# xbee-smd-breakout-1.net
KiCad netlist of a schematic drawn in EAGLE
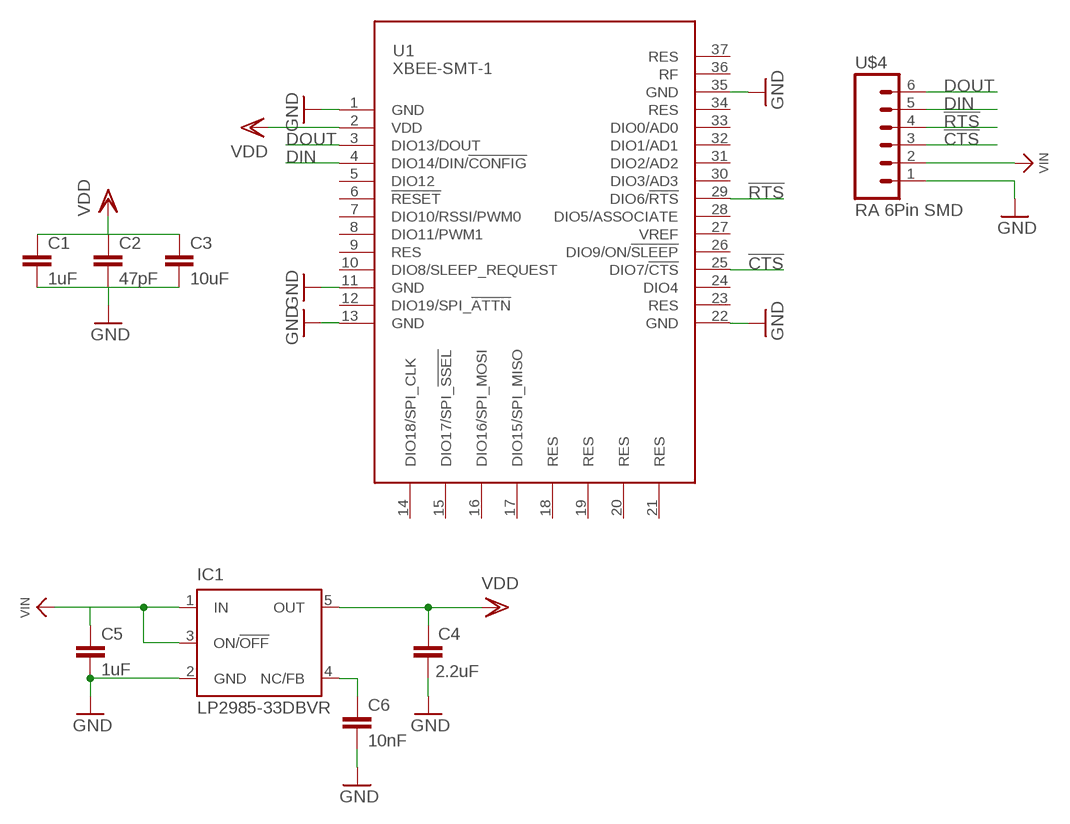
[diagram p0: schematic, sheet 1]

(export (version "E")
  (design (tool "Eeschema 10.0.6"))
  (components
    (comp (ref "C1")
      (value "1uF")
      (footprint "eagle-import:C0805")
      (libsource (lib "eagle-import") (part "C"))
    )
    (comp (ref "C2")
      (value "47pF")
      (footprint "eagle-import:C0805")
      (libsource (lib "eagle-import") (part "C"))
    )
    (comp (ref "C3")
      (value "10uF")
      (footprint "eagle-import:C0805")
      (libsource (lib "eagle-import") (part "C"))
    )
    (comp (ref "C4")
      (value "2.2uF")
      (footprint "eagle-import:C0805")
      (fields (field (name "MF") "MULTICOMP") (field (name "MPN") "MC0805B104K500CT"))
      (libsource (lib "eagle-import") (part "C-EUC0805"))
    )
    (comp (ref "C5")
      (value "1uF")
      (footprint "eagle-import:C0805")
      (libsource (lib "eagle-import") (part "C"))
    )
    (comp (ref "C6")
      (value "10nF")
      (footprint "eagle-import:C0805")
      (libsource (lib "eagle-import") (part "C"))
    )
    (comp (ref "IC1")
      (value "LP2985-33DBVR")
      (footprint "eagle-import:SOT23-DBV")
      (fields (field (name "MF") "ANALOG DEVICES") (field (name "MPN") "ADP3309ARTZ-3.3-R7"))
      (libsource (lib "eagle-import") (part "LP2985-XXDBVR33"))
    )
    (comp (ref "U$4")
      (value "RA 6Pin SMD")
      (footprint "eagle-import:1X06-SMD")
      (libsource (lib "eagle-import") (part "M06SMD"))
    )
    (comp (ref "U1")
      (value "XBEE-SMT-1")
      (footprint "eagle-import:XBEE-SMT")
      (libsource (lib "eagle-import") (part "XBEE-SMT-1"))
    )
  )
  (nets
    (net (code "1") (name "/DIN") (class "Default")
      (node (ref "U$4") (pin "5") (pinfunction "5_5") (pintype "passive"))
      (node (ref "U1") (pin "4") (pinfunction "DIO14/DIN/~{CONFIG}_4") (pintype "bidirectional"))
    )
    (net (code "2") (name "/DOUT") (class "Default")
      (node (ref "U$4") (pin "6") (pinfunction "6_6") (pintype "passive"))
      (node (ref "U1") (pin "3") (pinfunction "DIO13/DOUT_3") (pintype "bidirectional"))
    )
    (net (code "3") (name "/~{CTS}") (class "Default")
      (node (ref "U$4") (pin "3") (pinfunction "3_3") (pintype "passive"))
      (node (ref "U1") (pin "25") (pinfunction "DIO7/~{CTS}_25") (pintype "bidirectional"))
    )
    (net (code "4") (name "/~{RTS}") (class "Default")
      (node (ref "U$4") (pin "4") (pinfunction "4_4") (pintype "passive"))
      (node (ref "U1") (pin "29") (pinfunction "DIO6/~{RTS}_29") (pintype "input"))
    )
    (net (code "5") (name "GND") (class "Default")
      (node (ref "C1") (pin "2") (pinfunction "2_2") (pintype "passive"))
      (node (ref "C2") (pin "2") (pinfunction "2_2") (pintype "passive"))
      (node (ref "C3") (pin "2") (pinfunction "2_2") (pintype "passive"))
      (node (ref "C4") (pin "1") (pinfunction "1_1") (pintype "passive"))
      (node (ref "C5") (pin "2") (pinfunction "2_2") (pintype "passive"))
      (node (ref "C6") (pin "2") (pinfunction "2_2") (pintype "passive"))
      (node (ref "IC1") (pin "2") (pinfunction "GND_2") (pintype "power_in"))
      (node (ref "U$4") (pin "1") (pinfunction "1_1") (pintype "passive"))
      (node (ref "U1") (pin "1") (pinfunction "GND_1") (pintype "power_in"))
      (node (ref "U1") (pin "11") (pinfunction "GND_11") (pintype "power_in"))
      (node (ref "U1") (pin "13") (pinfunction "GND_13") (pintype "power_in"))
      (node (ref "U1") (pin "22") (pinfunction "GND_22") (pintype "power_in"))
      (node (ref "U1") (pin "35") (pinfunction "GND_35") (pintype "power_in"))
    )
    (net (code "6") (name "Net-(IC1-NC{slash}FB)") (class "Default")
      (node (ref "C6") (pin "1") (pinfunction "1_1") (pintype "passive"))
      (node (ref "IC1") (pin "4") (pinfunction "NC/FB_4") (pintype "passive"))
    )
    (net (code "7") (name "VDD") (class "Default")
      (node (ref "C1") (pin "1") (pinfunction "1_1") (pintype "passive"))
      (node (ref "C2") (pin "1") (pinfunction "1_1") (pintype "passive"))
      (node (ref "C3") (pin "1") (pinfunction "1_1") (pintype "passive"))
      (node (ref "C4") (pin "2") (pinfunction "2_2") (pintype "passive"))
      (node (ref "IC1") (pin "5") (pinfunction "OUT_5") (pintype "passive"))
      (node (ref "U1") (pin "2") (pinfunction "VDD_2") (pintype "power_in"))
    )
    (net (code "8") (name "VIN") (class "Default")
      (node (ref "C5") (pin "1") (pinfunction "1_1") (pintype "passive"))
      (node (ref "IC1") (pin "1") (pinfunction "IN_1") (pintype "input"))
      (node (ref "IC1") (pin "3") (pinfunction "ON/~{OFF}_3") (pintype "input"))
      (node (ref "U$4") (pin "2") (pinfunction "2_2") (pintype "passive"))
    )
    (net (code "9") (name "unconnected-(U1-DIO0{slash}AD0-Pad33)") (class "Default")
      (node (ref "U1") (pin "33") (pinfunction "DIO0/AD0_33") (pintype "bidirectional"))
    )
    (net (code "10") (name "unconnected-(U1-DIO1{slash}AD1-Pad32)") (class "Default")
      (node (ref "U1") (pin "32") (pinfunction "DIO1/AD1_32") (pintype "bidirectional"))
    )
    (net (code "11") (name "unconnected-(U1-DIO2{slash}AD2-Pad31)") (class "Default")
      (node (ref "U1") (pin "31") (pinfunction "DIO2/AD2_31") (pintype "bidirectional"))
    )
    (net (code "12") (name "unconnected-(U1-DIO3{slash}AD3-Pad30)") (class "Default")
      (node (ref "U1") (pin "30") (pinfunction "DIO3/AD3_30") (pintype "bidirectional"))
    )
    (net (code "13") (name "unconnected-(U1-DIO4-Pad24)") (class "Default")
      (node (ref "U1") (pin "24") (pinfunction "DIO4_24") (pintype "bidirectional"))
    )
    (net (code "14") (name "unconnected-(U1-DIO5{slash}ASSOCIATE-Pad28)") (class "Default")
      (node (ref "U1") (pin "28") (pinfunction "DIO5/ASSOCIATE_28") (pintype "bidirectional"))
    )
    (net (code "15") (name "unconnected-(U1-DIO8{slash}SLEEP_REQUEST-Pad10)") (class "Default")
      (node (ref "U1") (pin "10") (pinfunction "DIO8/SLEEP_REQUEST_10") (pintype "bidirectional"))
    )
    (net (code "16") (name "unconnected-(U1-DIO9{slash}ON{slash}~{SLEEP}-Pad26)") (class "Default")
      (node (ref "U1") (pin "26") (pinfunction "DIO9/ON/~{SLEEP}_26") (pintype "bidirectional"))
    )
    (net (code "17") (name "unconnected-(U1-DIO10{slash}RSSI{slash}PWM0-Pad7)") (class "Default")
      (node (ref "U1") (pin "7") (pinfunction "DIO10/RSSI/PWM0_7") (pintype "bidirectional"))
    )
    (net (code "18") (name "unconnected-(U1-DIO11{slash}PWM1-Pad8)") (class "Default")
      (node (ref "U1") (pin "8") (pinfunction "DIO11/PWM1_8") (pintype "bidirectional"))
    )
    (net (code "19") (name "unconnected-(U1-DIO12-Pad5)") (class "Default")
      (node (ref "U1") (pin "5") (pinfunction "DIO12_5") (pintype "bidirectional"))
    )
    (net (code "20") (name "unconnected-(U1-DIO15{slash}SPI_MISO-Pad17)") (class "Default")
      (node (ref "U1") (pin "17") (pinfunction "DIO15/SPI_MISO_17") (pintype "output"))
    )
    (net (code "21") (name "unconnected-(U1-DIO16{slash}SPI_MOSI-Pad16)") (class "Default")
      (node (ref "U1") (pin "16") (pinfunction "DIO16/SPI_MOSI_16") (pintype "input"))
    )
    (net (code "22") (name "unconnected-(U1-DIO17{slash}SPI_~{SSEL}-Pad15)") (class "Default")
      (node (ref "U1") (pin "15") (pinfunction "DIO17/SPI_~{SSEL}_15") (pintype "input"))
    )
    (net (code "23") (name "unconnected-(U1-DIO18{slash}SPI_CLK-Pad14)") (class "Default")
      (node (ref "U1") (pin "14") (pinfunction "DIO18/SPI_CLK_14") (pintype "input"))
    )
    (net (code "24") (name "unconnected-(U1-DIO19{slash}SPI_~{ATTN}-Pad12)") (class "Default")
      (node (ref "U1") (pin "12") (pinfunction "DIO19/SPI_~{ATTN}_12") (pintype "output"))
    )
    (net (code "25") (name "unconnected-(U1-RES-Pad9)") (class "Default")
      (node (ref "U1") (pin "9") (pinfunction "RES_9") (pintype "no_connect"))
    )
    (net (code "26") (name "unconnected-(U1-RES-Pad18)") (class "Default")
      (node (ref "U1") (pin "18") (pinfunction "RES_18") (pintype "no_connect"))
    )
    (net (code "27") (name "unconnected-(U1-RES-Pad19)") (class "Default")
      (node (ref "U1") (pin "19") (pinfunction "RES_19") (pintype "no_connect"))
    )
    (net (code "28") (name "unconnected-(U1-RES-Pad20)") (class "Default")
      (node (ref "U1") (pin "20") (pinfunction "RES_20") (pintype "no_connect"))
    )
    (net (code "29") (name "unconnected-(U1-RES-Pad21)") (class "Default")
      (node (ref "U1") (pin "21") (pinfunction "RES_21") (pintype "no_connect"))
    )
    (net (code "30") (name "unconnected-(U1-RES-Pad23)") (class "Default")
      (node (ref "U1") (pin "23") (pinfunction "RES_23") (pintype "no_connect"))
    )
    (net (code "31") (name "unconnected-(U1-RES-Pad34)") (class "Default")
      (node (ref "U1") (pin "34") (pinfunction "RES_34") (pintype "no_connect"))
    )
    (net (code "32") (name "unconnected-(U1-RES-Pad37)") (class "Default")
      (node (ref "U1") (pin "37") (pinfunction "RES_37") (pintype "no_connect"))
    )
    (net (code "33") (name "unconnected-(U1-RF-Pad36)") (class "Default")
      (node (ref "U1") (pin "36") (pinfunction "RF_36") (pintype "bidirectional"))
    )
    (net (code "34") (name "unconnected-(U1-VREF-Pad27)") (class "Default")
      (node (ref "U1") (pin "27") (pinfunction "VREF_27") (pintype "input"))
    )
    (net (code "35") (name "unconnected-(U1-~{RESET}-Pad6)") (class "Default")
      (node (ref "U1") (pin "6") (pinfunction "~{RESET}_6") (pintype "input"))
    )
  )
)
